# 9vRelay.net
KiCad netlist of a schematic drawn in EAGLE
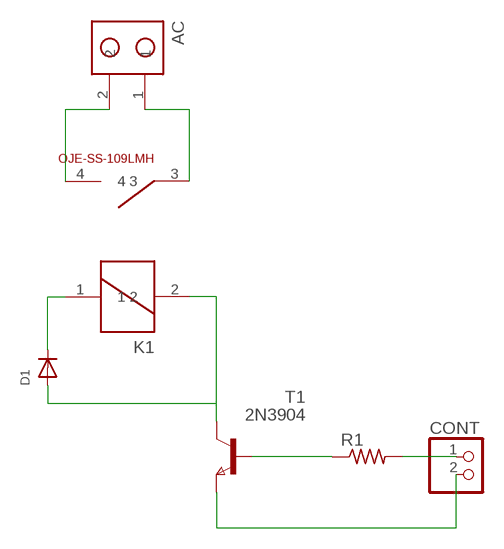
[diagram p0: schematic, sheet 1]

(export (version "E")
  (design (tool "Eeschema 10.0.6"))
  (components
    (comp (ref "AC")
      (value "TBLOCK1X2")
      (footprint "eagle-import:TBLOCK1X2")
      (libsource (lib "eagle-import") (part "TBLOCK1X2"))
    )
    (comp (ref "CONT")
      (value "PINHD-1X2")
      (footprint "eagle-import:1X02")
      (libsource (lib "eagle-import") (part "PINHD-1X2"))
    )
    (comp (ref "D1")
      (value "DIODESMA")
      (footprint "eagle-import:SMADIODE")
      (libsource (lib "eagle-import") (part "DIODESMA"))
    )
    (comp (ref "K1")
      (value "OJE-SS-109LMH")
      (footprint "eagle-import:OJE-SS-109LMH")
      (libsource (lib "eagle-import") (part "OJE-SS-109LMH"))
    )
    (comp (ref "R1")
      (value "R-US_R0603")
      (footprint "eagle-import:R0603")
      (libsource (lib "eagle-import") (part "R-US_R0603"))
    )
    (comp (ref "T1")
      (value "2N3904")
      (footprint "eagle-import:SOT-23")
      (libsource (lib "eagle-import") (part "FMMT451"))
    )
  )
  (nets
    (net (code "1") (name "Net-(AC-Pad1)") (class "Default")
      (node (ref "AC") (pin "1") (pinfunction "1_1") (pintype "bidirectional"))
      (node (ref "K1") (pin "3") (pinfunction "3_3") (pintype "bidirectional"))
    )
    (net (code "2") (name "Net-(AC-Pad2)") (class "Default")
      (node (ref "AC") (pin "2") (pinfunction "2_2") (pintype "bidirectional"))
      (node (ref "K1") (pin "4") (pinfunction "4_4") (pintype "bidirectional"))
    )
    (net (code "3") (name "Net-(CONT-Pad1)") (class "Default")
      (node (ref "CONT") (pin "1") (pinfunction "1_1") (pintype "passive"))
      (node (ref "R1") (pin "2") (pinfunction "2_2") (pintype "passive"))
    )
    (net (code "4") (name "Net-(D1-PadC)") (class "Default")
      (node (ref "D1") (pin "C") (pinfunction "C_C") (pintype "passive"))
      (node (ref "K1") (pin "1") (pinfunction "1_1") (pintype "bidirectional"))
    )
    (net (code "5") (name "Net-(T1-B)") (class "Default")
      (node (ref "R1") (pin "1") (pinfunction "1_1") (pintype "passive"))
      (node (ref "T1") (pin "3") (pinfunction "B_3") (pintype "passive"))
    )
    (net (code "6") (name "Net-(T1-C)") (class "Default")
      (node (ref "D1") (pin "A") (pinfunction "A_A") (pintype "passive"))
      (node (ref "K1") (pin "2") (pinfunction "2_2") (pintype "bidirectional"))
      (node (ref "T1") (pin "1") (pinfunction "C_1") (pintype "passive"))
    )
    (net (code "7") (name "Net-(T1-E)") (class "Default")
      (node (ref "CONT") (pin "2") (pinfunction "2_2") (pintype "passive"))
      (node (ref "T1") (pin "2") (pinfunction "E_2") (pintype "passive"))
    )
  )
)
